# 51.net
KiCad netlist of a schematic drawn in Altium Designer
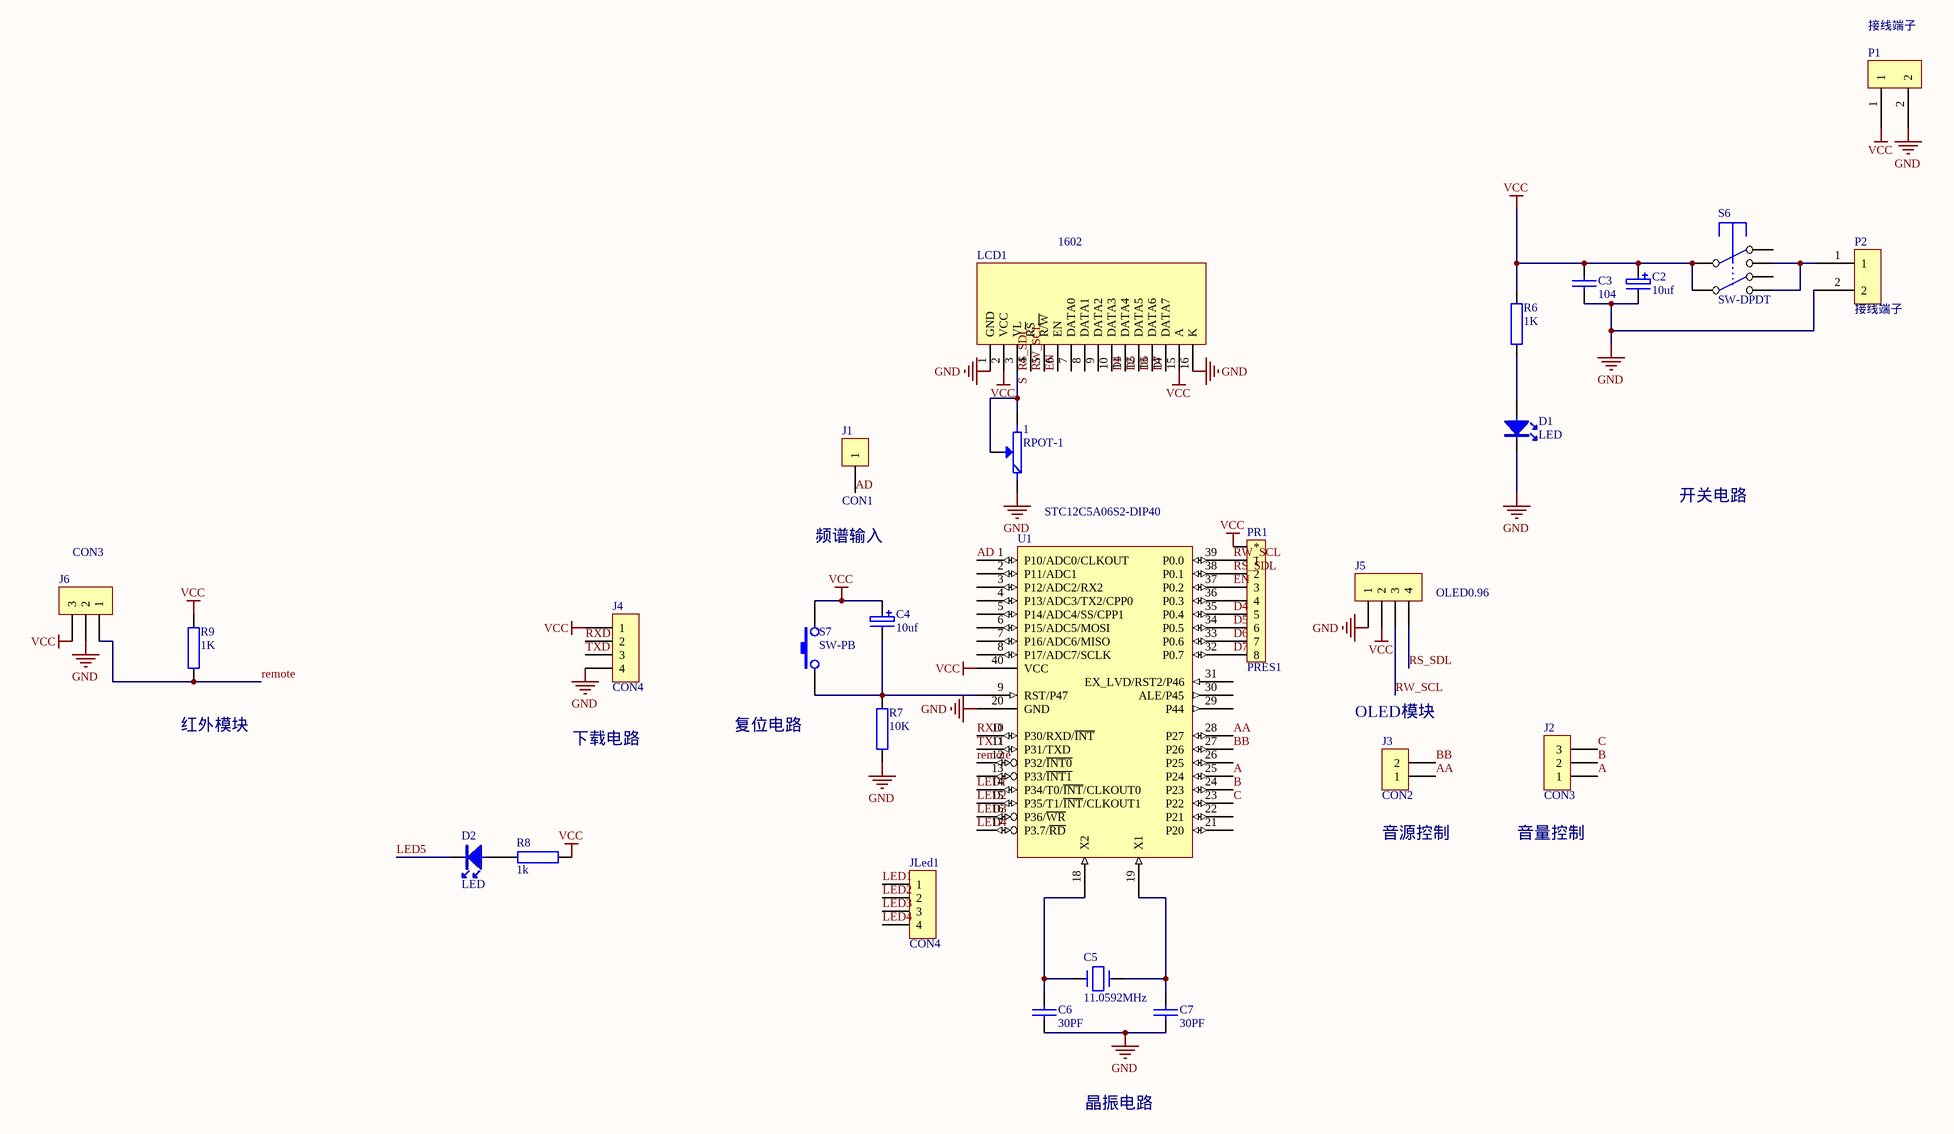
[diagram p0: 51单片机.SchDoc]

(export (version "E")
  (design (tool "Eeschema 10.0.6"))
  (components
    (comp (ref "1")
      (value "RPOT-1")
      (footprint "RVR-2")
      (description "普通电位器")
      (libsource (lib "电阻") (part "RPOT-1"))
    )
    (comp (ref "C2") (value "10uf") (footprint "CAO2") (libsource (lib "电容") (part "CAP3")))
    (comp (ref "C3") (value "104") (footprint "CAP2") (libsource (lib "电容") (part "CAP1")))
    (comp (ref "C4") (value "10uf") (footprint "CAO2") (libsource (lib "电容") (part "CAP3")))
    (comp (ref "C5") (value "11.0592MHz") (footprint "XTAL1") (libsource (lib "晶振") (part "CPY")))
    (comp (ref "C6") (value "30PF") (footprint "CAP2") (libsource (lib "电容") (part "CAP1")))
    (comp (ref "C7") (value "30PF") (footprint "CAP2") (libsource (lib "电容") (part "CAP1")))
    (comp (ref "D1") (value "LED") (footprint "LED2_B") (libsource (lib "二极管") (part "LED")))
    (comp (ref "D2") (value "LED") (footprint "LED2_B") (libsource (lib "二极管") (part "LED")))
    (comp (ref "J1")
      (value "CON1")
      (footprint "SIP-1")
      (description "Connector")
      (libsource (lib "排针") (part "CON1"))
    )
    (comp (ref "J2")
      (value "CON3")
      (footprint "sip-3")
      (description "Connector")
      (libsource (lib "排针") (part "CON3"))
    )
    (comp (ref "J3")
      (value "CON2")
      (footprint "sip-2")
      (description "Connector")
      (libsource (lib "排针") (part "CON2"))
    )
    (comp (ref "J4")
      (value "CON4")
      (footprint "sip-4")
      (description "Connector")
      (libsource (lib "排针") (part "CON4"))
    )
    (comp (ref "J5")
      (value "OLED0.96")
      (footprint "sip-4")
      (description "Connector")
      (libsource (lib "") (part "CON4_1"))
    )
    (comp (ref "J6")
      (value "CON3")
      (footprint "sip-3")
      (description "Connector")
      (libsource (lib "") (part "CON3_1"))
    )
    (comp (ref "JLed1")
      (value "CON4")
      (footprint "sip-4")
      (description "Connector")
      (libsource (lib "排针") (part "CON4"))
    )
    (comp (ref "LCD1") (value "1602") (footprint "1602") (libsource (lib "液晶_数码管") (part "1602")))
    (comp (ref "P1") (value "接线端子") (footprint "音频功放自画库:接线端子") (libsource (lib "音频功放自画库") (part "接线端子")))
    (comp (ref "P2") (value "接线端子") (footprint "音频功放自画库:接线端子") (libsource (lib "") (part "接线端子_1")))
    (comp (ref "PR1") (value "PRES1") (footprint "RP1") (libsource (lib "电阻") (part "PRES1")))
    (comp (ref "R6")
      (value "1K")
      (footprint "AXIAL0.4")
      (description "电阻")
      (libsource (lib "电阻") (part "RES"))
    )
    (comp (ref "R7")
      (value "10K")
      (footprint "AXIAL0.4")
      (description "电阻")
      (libsource (lib "电阻") (part "RES"))
    )
    (comp (ref "R8")
      (value "1k")
      (footprint "AXIAL0.4")
      (description "电阻")
      (libsource (lib "电阻") (part "RES"))
    )
    (comp (ref "R9")
      (value "1K")
      (footprint "AXIAL0.4")
      (description "电阻")
      (libsource (lib "电阻") (part "RES"))
    )
    (comp (ref "S6") (value "SW-DPDT") (footprint "SWH8*8") (libsource (lib "开关") (part "SW-DPDT")))
    (comp (ref "S7") (value "SW-PB") (footprint "SW6*6") (libsource (lib "开关") (part "SW-PB")))
    (comp (ref "U1")
      (value "STC12C5A06S2-DIP40")
      (footprint "DIP-40")
      (libsource (lib "单片机") (part "STC12C5A06S2-DIP40"))
    )
  )
  (nets
    (net (code "1") (name "/A") (class "Default")
      (node (ref "J2") (pin "1") (pinfunction "1_1") (pintype "passive"))
      (node (ref "U1") (pin "25") (pinfunction "P24_25") (pintype "bidirectional"))
    )
    (net (code "2") (name "/AA") (class "Default")
      (node (ref "J3") (pin "1") (pinfunction "1_1") (pintype "passive"))
      (node (ref "U1") (pin "28") (pinfunction "P27_28") (pintype "bidirectional"))
    )
    (net (code "3") (name "/AD") (class "Default")
      (node (ref "J1") (pin "1") (pinfunction "1_1") (pintype "passive"))
      (node (ref "U1") (pin "1") (pinfunction "P10/ADC0/CLKOUT_1") (pintype "bidirectional"))
    )
    (net (code "4") (name "/B") (class "Default")
      (node (ref "J2") (pin "2") (pinfunction "2_2") (pintype "passive"))
      (node (ref "U1") (pin "24") (pinfunction "P23_24") (pintype "bidirectional"))
    )
    (net (code "5") (name "/BB") (class "Default")
      (node (ref "J3") (pin "2") (pinfunction "2_2") (pintype "passive"))
      (node (ref "U1") (pin "27") (pinfunction "P26_27") (pintype "bidirectional"))
    )
    (net (code "6") (name "/C") (class "Default")
      (node (ref "J2") (pin "3") (pinfunction "3_3") (pintype "passive"))
      (node (ref "U1") (pin "23") (pinfunction "P22_23") (pintype "bidirectional"))
    )
    (net (code "7") (name "/D4") (class "Default")
      (node (ref "LCD1") (pin "11") (pinfunction "DATA4_11") (pintype "passive"))
      (node (ref "PR1") (pin "6") (pinfunction "5_6") (pintype "passive"))
      (node (ref "U1") (pin "35") (pinfunction "P0.4_35") (pintype "bidirectional"))
    )
    (net (code "8") (name "/D5") (class "Default")
      (node (ref "LCD1") (pin "12") (pinfunction "DATA5_12") (pintype "passive"))
      (node (ref "PR1") (pin "7") (pinfunction "6_7") (pintype "passive"))
      (node (ref "U1") (pin "34") (pinfunction "P0.5_34") (pintype "bidirectional"))
    )
    (net (code "9") (name "/D6") (class "Default")
      (node (ref "LCD1") (pin "13") (pinfunction "DATA6_13") (pintype "passive"))
      (node (ref "PR1") (pin "8") (pinfunction "7_8") (pintype "passive"))
      (node (ref "U1") (pin "33") (pinfunction "P0.6_33") (pintype "bidirectional"))
    )
    (net (code "10") (name "/D7") (class "Default")
      (node (ref "LCD1") (pin "14") (pinfunction "DATA7_14") (pintype "passive"))
      (node (ref "PR1") (pin "9") (pinfunction "8_9") (pintype "passive"))
      (node (ref "U1") (pin "32") (pinfunction "P0.7_32") (pintype "bidirectional"))
    )
    (net (code "11") (name "/EN") (class "Default")
      (node (ref "LCD1") (pin "6") (pinfunction "EN_6") (pintype "passive"))
      (node (ref "PR1") (pin "4") (pinfunction "3_4") (pintype "passive"))
      (node (ref "U1") (pin "37") (pinfunction "P0.2_37") (pintype "bidirectional"))
    )
    (net (code "12") (name "/LED1") (class "Default")
      (node (ref "JLed1") (pin "1") (pinfunction "1_1") (pintype "passive"))
      (node (ref "U1") (pin "14") (pinfunction "P34/T0/~{INT}/CLKOUT0_14") (pintype "bidirectional"))
    )
    (net (code "13") (name "/LED2") (class "Default")
      (node (ref "JLed1") (pin "2") (pinfunction "2_2") (pintype "passive"))
      (node (ref "U1") (pin "15") (pinfunction "P35/T1/~{INT}/CLKOUT1_15") (pintype "bidirectional"))
    )
    (net (code "14") (name "/LED3") (class "Default")
      (node (ref "JLed1") (pin "3") (pinfunction "3_3") (pintype "passive"))
      (node (ref "U1") (pin "16") (pinfunction "P36/~{WR}_16") (pintype "bidirectional"))
    )
    (net (code "15") (name "/LED4") (class "Default")
      (node (ref "JLed1") (pin "4") (pinfunction "4_4") (pintype "passive"))
      (node (ref "U1") (pin "17") (pinfunction "P3.7/~{RD}_17") (pintype "bidirectional"))
    )
    (net (code "16") (name "/LED5") (class "Default")
      (node (ref "D2") (pin "2") (pinfunction "2_2") (pintype "passive"))
    )
    (net (code "17") (name "/RS_SDL") (class "Default")
      (node (ref "J5") (pin "4") (pinfunction "4_4") (pintype "passive"))
      (node (ref "LCD1") (pin "4") (pinfunction "R~{S}_4") (pintype "passive"))
      (node (ref "PR1") (pin "3") (pinfunction "2_3") (pintype "passive"))
      (node (ref "U1") (pin "38") (pinfunction "P0.1_38") (pintype "bidirectional"))
    )
    (net (code "18") (name "/RW_SCL") (class "Default")
      (node (ref "J5") (pin "3") (pinfunction "3_3") (pintype "passive"))
      (node (ref "LCD1") (pin "5") (pinfunction "R/~{W}_5") (pintype "passive"))
      (node (ref "PR1") (pin "2") (pinfunction "1_2") (pintype "passive"))
      (node (ref "U1") (pin "39") (pinfunction "P0.0_39") (pintype "bidirectional"))
    )
    (net (code "19") (name "/RXD") (class "Default")
      (node (ref "J4") (pin "2") (pinfunction "2_2") (pintype "passive"))
      (node (ref "U1") (pin "10") (pinfunction "P30/RXD/~{INT}_10") (pintype "bidirectional"))
    )
    (net (code "21") (name "/TXD") (class "Default")
      (node (ref "J4") (pin "3") (pinfunction "3_3") (pintype "passive"))
      (node (ref "U1") (pin "11") (pinfunction "P31/TXD_11") (pintype "bidirectional"))
    )
    (net (code "22") (name "/remote") (class "Default")
      (node (ref "J6") (pin "1") (pinfunction "1_1") (pintype "passive"))
      (node (ref "R9") (pin "1") (pinfunction "1_1") (pintype "passive"))
      (node (ref "U1") (pin "12") (pinfunction "P32/~{INT0}_12") (pintype "bidirectional"))
    )
    (net (code "23") (name "GND") (class "Default")
      (node (ref "1") (pin "1") (pinfunction "1_1") (pintype "passive"))
      (node (ref "C2") (pin "2") (pintype "passive"))
      (node (ref "C3") (pin "2") (pinfunction "2_2") (pintype "passive"))
      (node (ref "C6") (pin "2") (pinfunction "2_2") (pintype "passive"))
      (node (ref "C7") (pin "2") (pinfunction "2_2") (pintype "passive"))
      (node (ref "D1") (pin "2") (pinfunction "2_2") (pintype "passive"))
      (node (ref "J4") (pin "4") (pinfunction "4_4") (pintype "passive"))
      (node (ref "J5") (pin "1") (pinfunction "1_1") (pintype "passive"))
      (node (ref "J6") (pin "2") (pinfunction "2_2") (pintype "passive"))
      (node (ref "LCD1") (pin "1") (pinfunction "GND_1") (pintype "passive"))
      (node (ref "LCD1") (pin "16") (pinfunction "K_16") (pintype "passive"))
      (node (ref "P1") (pin "2") (pinfunction "2_2") (pintype "passive"))
      (node (ref "P2") (pin "2") (pinfunction "2_2") (pintype "passive"))
      (node (ref "R7") (pin "1") (pinfunction "1_1") (pintype "passive"))
      (node (ref "U1") (pin "20") (pinfunction "GND_20") (pintype "power_in"))
    )
    (net (code "24") (name "Net-(1-M)") (class "Default")
      (node (ref "1") (pin "2") (pinfunction "M_2") (pintype "passive"))
      (node (ref "1") (pin "3") (pinfunction "3_3") (pintype "passive"))
      (node (ref "LCD1") (pin "3") (pinfunction "VL_3") (pintype "passive"))
    )
    (net (code "25") (name "Net-(D1-Pad1)") (class "Default")
      (node (ref "D1") (pin "1") (pinfunction "1_1") (pintype "passive"))
      (node (ref "R6") (pin "1") (pinfunction "1_1") (pintype "passive"))
    )
    (net (code "26") (name "Net-(D2-Pad1)") (class "Default")
      (node (ref "D2") (pin "1") (pinfunction "1_1") (pintype "passive"))
      (node (ref "R8") (pin "2") (pinfunction "2_2") (pintype "passive"))
    )
    (net (code "27") (name "Net-(P2-Pad1)") (class "Default")
      (node (ref "P2") (pin "1") (pinfunction "1_1") (pintype "passive"))
      (node (ref "S6") (pin "3") (pinfunction "3_3") (pintype "passive"))
      (node (ref "S6") (pin "4") (pinfunction "4_4") (pintype "passive"))
    )
    (net (code "28") (name "Net-(PR1-4)") (class "Default")
      (node (ref "PR1") (pin "5") (pinfunction "4_5") (pintype "passive"))
      (node (ref "U1") (pin "36") (pinfunction "P0.3_36") (pintype "bidirectional"))
    )
    (net (code "29") (name "Net-(U1-RST{slash}P47)") (class "Default")
      (node (ref "C4") (pin "2") (pintype "passive"))
      (node (ref "R7") (pin "2") (pinfunction "2_2") (pintype "passive"))
      (node (ref "S7") (pin "1") (pinfunction "1_1") (pintype "passive"))
      (node (ref "U1") (pin "9") (pinfunction "RST/P47_9") (pintype "input"))
    )
    (net (code "30") (name "Net-(U1-X1)") (class "Default")
      (node (ref "C5") (pin "2") (pintype "passive"))
      (node (ref "C7") (pin "1") (pinfunction "1_1") (pintype "passive"))
      (node (ref "U1") (pin "19") (pinfunction "X1_19") (pintype "input"))
    )
    (net (code "31") (name "Net-(U1-X2)") (class "Default")
      (node (ref "C5") (pin "1") (pintype "passive"))
      (node (ref "C6") (pin "1") (pinfunction "1_1") (pintype "passive"))
      (node (ref "U1") (pin "18") (pinfunction "X2_18") (pintype "input"))
    )
    (net (code "32") (name "VCC") (class "Default")
      (node (ref "C2") (pin "1") (pintype "passive"))
      (node (ref "C3") (pin "1") (pinfunction "1_1") (pintype "passive"))
      (node (ref "C4") (pin "1") (pintype "passive"))
      (node (ref "J4") (pin "1") (pinfunction "1_1") (pintype "passive"))
      (node (ref "J5") (pin "2") (pinfunction "2_2") (pintype "passive"))
      (node (ref "J6") (pin "3") (pinfunction "3_3") (pintype "passive"))
      (node (ref "LCD1") (pin "15") (pinfunction "A_15") (pintype "passive"))
      (node (ref "LCD1") (pin "2") (pinfunction "VCC_2") (pintype "passive"))
      (node (ref "P1") (pin "1") (pinfunction "1_1") (pintype "passive"))
      (node (ref "PR1") (pin "1") (pinfunction "*_1") (pintype "passive"))
      (node (ref "R6") (pin "2") (pinfunction "2_2") (pintype "passive"))
      (node (ref "R8") (pin "1") (pinfunction "1_1") (pintype "passive"))
      (node (ref "R9") (pin "2") (pinfunction "2_2") (pintype "passive"))
      (node (ref "S6") (pin "2") (pinfunction "2_2") (pintype "passive"))
      (node (ref "S6") (pin "5") (pinfunction "5_5") (pintype "passive"))
      (node (ref "S7") (pin "2") (pinfunction "2_2") (pintype "passive"))
      (node (ref "U1") (pin "40") (pinfunction "VCC_40") (pintype "power_in"))
    )
    (net (code "33") (name "unconnected-(LCD1-DATA0-Pad7)") (class "Default")
      (node (ref "LCD1") (pin "7") (pinfunction "DATA0_7") (pintype "passive"))
    )
    (net (code "34") (name "unconnected-(LCD1-DATA1-Pad8)") (class "Default")
      (node (ref "LCD1") (pin "8") (pinfunction "DATA1_8") (pintype "passive"))
    )
    (net (code "35") (name "unconnected-(LCD1-DATA2-Pad9)") (class "Default")
      (node (ref "LCD1") (pin "9") (pinfunction "DATA2_9") (pintype "passive"))
    )
    (net (code "36") (name "unconnected-(LCD1-DATA3-Pad10)") (class "Default")
      (node (ref "LCD1") (pin "10") (pinfunction "DATA3_10") (pintype "passive"))
    )
    (net (code "37") (name "unconnected-(S6-Pad1)") (class "Default")
      (node (ref "S6") (pin "1") (pinfunction "1_1") (pintype "passive"))
    )
    (net (code "38") (name "unconnected-(S6-Pad6)") (class "Default")
      (node (ref "S6") (pin "6") (pinfunction "6_6") (pintype "passive"))
    )
    (net (code "39") (name "unconnected-(U1-ALE{slash}P45-Pad30)") (class "Default")
      (node (ref "U1") (pin "30") (pinfunction "ALE/P45_30") (pintype "output"))
    )
    (net (code "40") (name "unconnected-(U1-EX_LVD{slash}RST2{slash}P46-Pad31)") (class "Default")
      (node (ref "U1") (pin "31") (pinfunction "EX_LVD/RST2/P46_31") (pintype "input"))
    )
    (net (code "41") (name "unconnected-(U1-P11{slash}ADC1-Pad2)") (class "Default")
      (node (ref "U1") (pin "2") (pinfunction "P11/ADC1_2") (pintype "bidirectional"))
    )
    (net (code "42") (name "unconnected-(U1-P12{slash}ADC2{slash}RX2-Pad3)") (class "Default")
      (node (ref "U1") (pin "3") (pinfunction "P12/ADC2/RX2_3") (pintype "bidirectional"))
    )
    (net (code "43") (name "unconnected-(U1-P13{slash}ADC3{slash}TX2{slash}CPP0-Pad4)") (class "Default")
      (node (ref "U1") (pin "4") (pinfunction "P13/ADC3/TX2/CPP0_4") (pintype "bidirectional"))
    )
    (net (code "44") (name "unconnected-(U1-P14{slash}ADC4{slash}SS{slash}CPP1-Pad5)") (class "Default")
      (node (ref "U1") (pin "5") (pinfunction "P14/ADC4/SS/CPP1_5") (pintype "bidirectional"))
    )
    (net (code "45") (name "unconnected-(U1-P15{slash}ADC5{slash}MOSI-Pad6)") (class "Default")
      (node (ref "U1") (pin "6") (pinfunction "P15/ADC5/MOSI_6") (pintype "bidirectional"))
    )
    (net (code "46") (name "unconnected-(U1-P16{slash}ADC6{slash}MISO-Pad7)") (class "Default")
      (node (ref "U1") (pin "7") (pinfunction "P16/ADC6/MISO_7") (pintype "bidirectional"))
    )
    (net (code "47") (name "unconnected-(U1-P17{slash}ADC7{slash}SCLK-Pad8)") (class "Default")
      (node (ref "U1") (pin "8") (pinfunction "P17/ADC7/SCLK_8") (pintype "bidirectional"))
    )
    (net (code "48") (name "unconnected-(U1-P20-Pad21)") (class "Default")
      (node (ref "U1") (pin "21") (pinfunction "P20_21") (pintype "bidirectional"))
    )
    (net (code "49") (name "unconnected-(U1-P21-Pad22)") (class "Default")
      (node (ref "U1") (pin "22") (pinfunction "P21_22") (pintype "bidirectional"))
    )
    (net (code "50") (name "unconnected-(U1-P25-Pad26)") (class "Default")
      (node (ref "U1") (pin "26") (pinfunction "P25_26") (pintype "bidirectional"))
    )
    (net (code "51") (name "unconnected-(U1-P33{slash}~{INT1}-Pad13)") (class "Default")
      (node (ref "U1") (pin "13") (pinfunction "P33/~{INT1}_13") (pintype "bidirectional"))
    )
    (net (code "52") (name "unconnected-(U1-P44-Pad29)") (class "Default")
      (node (ref "U1") (pin "29") (pinfunction "P44_29") (pintype "output"))
    )
  )
)
